# Template.net
KiCad netlist of a schematic drawn in Altium Designer
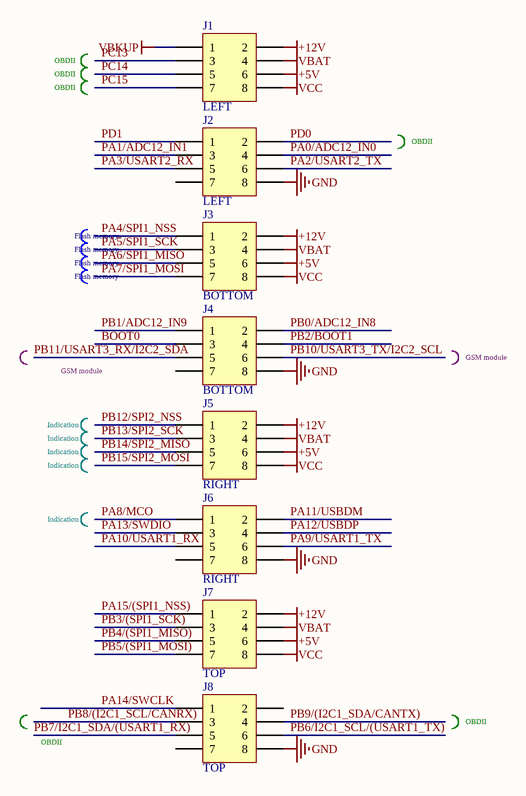
[diagram p0: Template.SchDoc]

(export (version "E")
  (design (tool "Eeschema 10.0.6"))
  (components
    (comp (ref "J1")
      (value "LEFT")
      (footprint "PBDM-8")
      (description "2x4-pin header, pitch 2.54 mm")
      (fields (field (name "PARTNUMBER") "PBDM-8") (field (name "AUTHOR") "oiezhov"))
      (libsource (lib "Library") (part "8-pin dual row connector"))
    )
    (comp (ref "J2")
      (value "LEFT")
      (footprint "PBDM-8")
      (description "2x4-pin header, pitch 2.54 mm")
      (fields (field (name "PARTNUMBER") "PBDM-8") (field (name "AUTHOR") "oiezhov"))
      (libsource (lib "Library") (part "8-pin dual row connector"))
    )
    (comp (ref "J3")
      (value "BOTTOM")
      (footprint "PBDM-8")
      (description "2x4-pin header, pitch 2.54 mm")
      (fields (field (name "PARTNUMBER") "PBDM-8") (field (name "AUTHOR") "oiezhov"))
      (libsource (lib "Library") (part "8-pin dual row connector"))
    )
    (comp (ref "J4")
      (value "BOTTOM")
      (footprint "PBDM-8")
      (description "2x4-pin header, pitch 2.54 mm")
      (fields (field (name "PARTNUMBER") "PBDM-8") (field (name "AUTHOR") "oiezhov"))
      (libsource (lib "Library") (part "8-pin dual row connector"))
    )
    (comp (ref "J5")
      (value "RIGHT")
      (footprint "PBDM-8")
      (description "2x4-pin header, pitch 2.54 mm")
      (fields (field (name "PARTNUMBER") "PBDM-8") (field (name "AUTHOR") "oiezhov"))
      (libsource (lib "Library") (part "8-pin dual row connector"))
    )
    (comp (ref "J6")
      (value "RIGHT")
      (footprint "PBDM-8")
      (description "2x4-pin header, pitch 2.54 mm")
      (fields (field (name "PARTNUMBER") "PBDM-8") (field (name "AUTHOR") "oiezhov"))
      (libsource (lib "Library") (part "8-pin dual row connector"))
    )
    (comp (ref "J7")
      (value "TOP")
      (footprint "PBDM-8")
      (description "2x4-pin header, pitch 2.54 mm")
      (fields (field (name "PARTNUMBER") "PBDM-8") (field (name "AUTHOR") "oiezhov"))
      (libsource (lib "Library") (part "8-pin dual row connector"))
    )
    (comp (ref "J8")
      (value "TOP")
      (footprint "PBDM-8")
      (description "2x4-pin header, pitch 2.54 mm")
      (fields (field (name "PARTNUMBER") "PBDM-8") (field (name "AUTHOR") "oiezhov"))
      (libsource (lib "Library") (part "8-pin dual row connector"))
    )
  )
  (nets
    (net (code "1") (name "+5V") (class "Default")
      (node (ref "J1") (pin "6") (pinfunction "6_6") (pintype "passive"))
      (node (ref "J3") (pin "6") (pinfunction "6_6") (pintype "passive"))
      (node (ref "J5") (pin "6") (pinfunction "6_6") (pintype "passive"))
      (node (ref "J7") (pin "6") (pinfunction "6_6") (pintype "passive"))
    )
    (net (code "2") (name "+12V") (class "Default")
      (node (ref "J1") (pin "2") (pinfunction "2_2") (pintype "passive"))
      (node (ref "J3") (pin "2") (pinfunction "2_2") (pintype "passive"))
      (node (ref "J5") (pin "2") (pinfunction "2_2") (pintype "passive"))
      (node (ref "J7") (pin "2") (pinfunction "2_2") (pintype "passive"))
    )
    (net (code "3") (name "/BOOT0") (class "Default")
      (node (ref "J4") (pin "3") (pinfunction "3_3") (pintype "passive"))
    )
    (net (code "4") (name "/PA0{slash}ADC12_IN0") (class "Default")
      (node (ref "J2") (pin "4") (pinfunction "4_4") (pintype "passive"))
    )
    (net (code "5") (name "/PA1{slash}ADC12_IN1") (class "Default")
      (node (ref "J2") (pin "3") (pinfunction "3_3") (pintype "passive"))
    )
    (net (code "6") (name "/PA2{slash}USART2_TX") (class "Default")
      (node (ref "J2") (pin "6") (pinfunction "6_6") (pintype "passive"))
    )
    (net (code "7") (name "/PA3{slash}USART2_RX") (class "Default")
      (node (ref "J2") (pin "5") (pinfunction "5_5") (pintype "passive"))
    )
    (net (code "8") (name "/PA4{slash}SPI1_NSS") (class "Default")
      (node (ref "J3") (pin "1") (pinfunction "1_1") (pintype "passive"))
    )
    (net (code "9") (name "/PA5{slash}SPI1_SCK") (class "Default")
      (node (ref "J3") (pin "3") (pinfunction "3_3") (pintype "passive"))
    )
    (net (code "10") (name "/PA6{slash}SPI1_MISO") (class "Default")
      (node (ref "J3") (pin "5") (pinfunction "5_5") (pintype "passive"))
    )
    (net (code "11") (name "/PA7{slash}SPI1_MOSI") (class "Default")
      (node (ref "J3") (pin "7") (pinfunction "7_7") (pintype "passive"))
    )
    (net (code "12") (name "/PA8{slash}MCO") (class "Default")
      (node (ref "J6") (pin "1") (pinfunction "1_1") (pintype "passive"))
    )
    (net (code "13") (name "/PA9{slash}USART1_TX") (class "Default")
      (node (ref "J6") (pin "6") (pinfunction "6_6") (pintype "passive"))
    )
    (net (code "14") (name "/PA10{slash}USART1_RX") (class "Default")
      (node (ref "J6") (pin "5") (pinfunction "5_5") (pintype "passive"))
    )
    (net (code "15") (name "/PA11{slash}USBDM") (class "Default")
      (node (ref "J6") (pin "2") (pinfunction "2_2") (pintype "passive"))
    )
    (net (code "16") (name "/PA12{slash}USBDP") (class "Default")
      (node (ref "J6") (pin "4") (pinfunction "4_4") (pintype "passive"))
    )
    (net (code "17") (name "/PA13{slash}SWDIO") (class "Default")
      (node (ref "J6") (pin "3") (pinfunction "3_3") (pintype "passive"))
    )
    (net (code "18") (name "/PA14{slash}SWCLK") (class "Default")
      (node (ref "J8") (pin "1") (pinfunction "1_1") (pintype "passive"))
    )
    (net (code "19") (name "/PA15{slash}(SPI1_NSS)") (class "Default")
      (node (ref "J7") (pin "1") (pinfunction "1_1") (pintype "passive"))
    )
    (net (code "20") (name "/PB0{slash}ADC12_IN8") (class "Default")
      (node (ref "J4") (pin "2") (pinfunction "2_2") (pintype "passive"))
    )
    (net (code "21") (name "/PB1{slash}ADC12_IN9") (class "Default")
      (node (ref "J4") (pin "1") (pinfunction "1_1") (pintype "passive"))
    )
    (net (code "22") (name "/PB2{slash}BOOT1") (class "Default")
      (node (ref "J4") (pin "4") (pinfunction "4_4") (pintype "passive"))
    )
    (net (code "23") (name "/PB3{slash}(SPI1_SCK)") (class "Default")
      (node (ref "J7") (pin "3") (pinfunction "3_3") (pintype "passive"))
    )
    (net (code "24") (name "/PB4{slash}(SPI1_MISO)") (class "Default")
      (node (ref "J7") (pin "5") (pinfunction "5_5") (pintype "passive"))
    )
    (net (code "25") (name "/PB5{slash}(SPI1_MOSI)") (class "Default")
      (node (ref "J7") (pin "7") (pinfunction "7_7") (pintype "passive"))
    )
    (net (code "26") (name "/PB6{slash}I2C1_SCL{slash}(USART1_TX)") (class "Default")
      (node (ref "J8") (pin "6") (pinfunction "6_6") (pintype "passive"))
    )
    (net (code "27") (name "/PB7{slash}I2C1_SDA{slash}(USART1_RX)") (class "Default")
      (node (ref "J8") (pin "5") (pinfunction "5_5") (pintype "passive"))
    )
    (net (code "28") (name "/PB8{slash}(I2C1_SCL{slash}CANRX)") (class "Default")
      (node (ref "J8") (pin "3") (pinfunction "3_3") (pintype "passive"))
    )
    (net (code "29") (name "/PB9{slash}(I2C1_SDA{slash}CANTX)") (class "Default")
      (node (ref "J8") (pin "4") (pinfunction "4_4") (pintype "passive"))
    )
    (net (code "30") (name "/PB10{slash}USART3_TX{slash}I2C2_SCL") (class "Default")
      (node (ref "J4") (pin "6") (pinfunction "6_6") (pintype "passive"))
    )
    (net (code "31") (name "/PB11{slash}USART3_RX{slash}I2C2_SDA") (class "Default")
      (node (ref "J4") (pin "5") (pinfunction "5_5") (pintype "passive"))
    )
    (net (code "32") (name "/PB12{slash}SPI2_NSS") (class "Default")
      (node (ref "J5") (pin "1") (pinfunction "1_1") (pintype "passive"))
    )
    (net (code "33") (name "/PB13{slash}SPI2_SCK") (class "Default")
      (node (ref "J5") (pin "3") (pinfunction "3_3") (pintype "passive"))
    )
    (net (code "34") (name "/PB14{slash}SPI2_MISO") (class "Default")
      (node (ref "J5") (pin "5") (pinfunction "5_5") (pintype "passive"))
    )
    (net (code "35") (name "/PB15{slash}SPI2_MOSI") (class "Default")
      (node (ref "J5") (pin "7") (pinfunction "7_7") (pintype "passive"))
    )
    (net (code "36") (name "/PC13") (class "Default")
      (node (ref "J1") (pin "3") (pinfunction "3_3") (pintype "passive"))
    )
    (net (code "37") (name "/PC14") (class "Default")
      (node (ref "J1") (pin "5") (pinfunction "5_5") (pintype "passive"))
    )
    (net (code "38") (name "/PC15") (class "Default")
      (node (ref "J1") (pin "7") (pinfunction "7_7") (pintype "passive"))
    )
    (net (code "39") (name "/PD0") (class "Default")
      (node (ref "J2") (pin "2") (pinfunction "2_2") (pintype "passive"))
    )
    (net (code "40") (name "/PD1") (class "Default")
      (node (ref "J2") (pin "1") (pinfunction "1_1") (pintype "passive"))
    )
    (net (code "41") (name "GND") (class "Default")
      (node (ref "J2") (pin "8") (pinfunction "8_8") (pintype "passive"))
      (node (ref "J4") (pin "8") (pinfunction "8_8") (pintype "passive"))
      (node (ref "J6") (pin "8") (pinfunction "8_8") (pintype "passive"))
      (node (ref "J8") (pin "8") (pinfunction "8_8") (pintype "passive"))
    )
    (net (code "42") (name "VBAT") (class "Default")
      (node (ref "J1") (pin "4") (pinfunction "4_4") (pintype "passive"))
      (node (ref "J3") (pin "4") (pinfunction "4_4") (pintype "passive"))
      (node (ref "J5") (pin "4") (pinfunction "4_4") (pintype "passive"))
      (node (ref "J7") (pin "4") (pinfunction "4_4") (pintype "passive"))
    )
    (net (code "43") (name "VBKUP") (class "Default")
      (node (ref "J1") (pin "1") (pinfunction "1_1") (pintype "passive"))
    )
    (net (code "44") (name "VCC") (class "Default")
      (node (ref "J1") (pin "8") (pinfunction "8_8") (pintype "passive"))
      (node (ref "J3") (pin "8") (pinfunction "8_8") (pintype "passive"))
      (node (ref "J5") (pin "8") (pinfunction "8_8") (pintype "passive"))
      (node (ref "J7") (pin "8") (pinfunction "8_8") (pintype "passive"))
    )
    (net (code "45") (name "unconnected-(J2-Pad7)") (class "Default")
      (node (ref "J2") (pin "7") (pinfunction "7_7") (pintype "passive"))
    )
    (net (code "46") (name "unconnected-(J4-Pad7)") (class "Default")
      (node (ref "J4") (pin "7") (pinfunction "7_7") (pintype "passive"))
    )
    (net (code "47") (name "unconnected-(J6-Pad7)") (class "Default")
      (node (ref "J6") (pin "7") (pinfunction "7_7") (pintype "passive"))
    )
    (net (code "48") (name "unconnected-(J8-Pad2)") (class "Default")
      (node (ref "J8") (pin "2") (pinfunction "2_2") (pintype "passive"))
    )
    (net (code "49") (name "unconnected-(J8-Pad7)") (class "Default")
      (node (ref "J8") (pin "7") (pinfunction "7_7") (pintype "passive"))
    )
  )
)
